# schematic_v_2.net
KiCad netlist of a schematic drawn in EAGLE
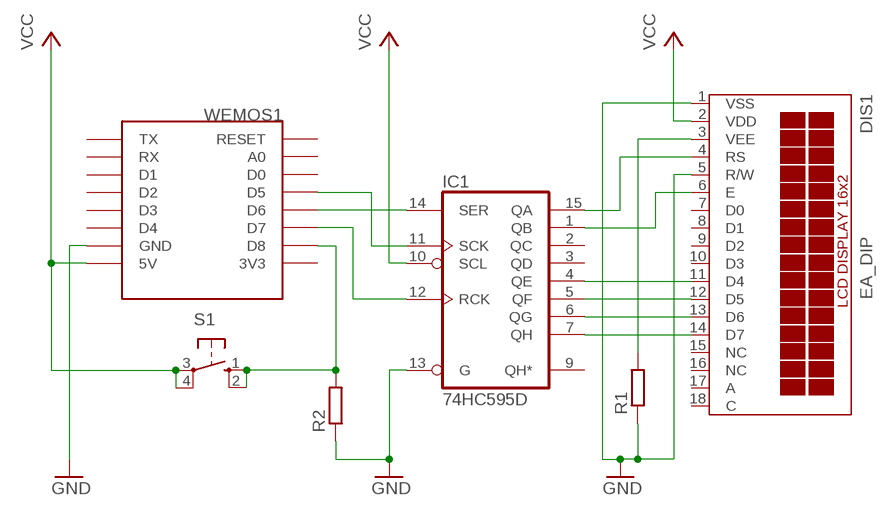
[diagram p0: schematic, sheet 1]

(export (version "E")
  (design (tool "Eeschema 10.0.6"))
  (components
    (comp (ref "DIS1")
      (value "EA_DIP")
      (footprint "eagle-import:EA_DIP")
      (libsource (lib "eagle-import") (part "EA_DIP"))
    )
    (comp (ref "IC1")
      (value "74HC595D")
      (footprint "eagle-import:SO16")
      (libsource (lib "eagle-import") (part "74595DHC"))
    )
    (comp (ref "R1")
      (value "R-EU_0204/2V")
      (footprint "eagle-import:0204V")
      (libsource (lib "eagle-import") (part "R-EU_0204/2V"))
    )
    (comp (ref "R2")
      (value "R-EU_0204/2V")
      (footprint "eagle-import:0204V")
      (libsource (lib "eagle-import") (part "R-EU_0204/2V"))
    )
    (comp (ref "S1")
      (value "10-XX")
      (footprint "eagle-import:B3F-10XX")
      (fields (field (name "MPN") "B3F-1000"))
      (libsource (lib "eagle-import") (part "10-XX"))
    )
    (comp (ref "WEMOS1")
      (value "WEMOS-D1-MINI")
      (footprint "eagle-import:WEMOS-D1-MINI")
      (libsource (lib "eagle-import") (part "WEMOS-D1-MINI"))
    )
  )
  (nets
    (net (code "1") (name "GND") (class "Default")
      (node (ref "DIS1") (pin "1") (pinfunction "VSS_1") (pintype "power_in"))
      (node (ref "DIS1") (pin "5") (pinfunction "R/W_5") (pintype "input"))
      (node (ref "IC1") (pin "13") (pinfunction "G_13") (pintype "input"))
      (node (ref "R1") (pin "1") (pinfunction "1_1") (pintype "passive"))
      (node (ref "R2") (pin "1") (pinfunction "1_1") (pintype "passive"))
      (node (ref "WEMOS1") (pin "GND") (pinfunction "GND_GND") (pintype "bidirectional"))
    )
    (net (code "2") (name "Net-(DIS1-D4)") (class "Default")
      (node (ref "DIS1") (pin "11") (pinfunction "D4_11") (pintype "input"))
      (node (ref "IC1") (pin "4") (pinfunction "QE_4") (pintype "tri_state"))
    )
    (net (code "3") (name "Net-(DIS1-D5)") (class "Default")
      (node (ref "DIS1") (pin "12") (pinfunction "D5_12") (pintype "input"))
      (node (ref "IC1") (pin "5") (pinfunction "QF_5") (pintype "tri_state"))
    )
    (net (code "4") (name "Net-(DIS1-D6)") (class "Default")
      (node (ref "DIS1") (pin "13") (pinfunction "D6_13") (pintype "input"))
      (node (ref "IC1") (pin "6") (pinfunction "QG_6") (pintype "tri_state"))
    )
    (net (code "5") (name "Net-(DIS1-D7)") (class "Default")
      (node (ref "DIS1") (pin "14") (pinfunction "D7_14") (pintype "input"))
      (node (ref "IC1") (pin "7") (pinfunction "QH_7") (pintype "tri_state"))
    )
    (net (code "6") (name "Net-(DIS1-E)") (class "Default")
      (node (ref "DIS1") (pin "6") (pinfunction "E_6") (pintype "input"))
      (node (ref "IC1") (pin "1") (pinfunction "QB_1") (pintype "tri_state"))
    )
    (net (code "7") (name "Net-(DIS1-RS)") (class "Default")
      (node (ref "DIS1") (pin "4") (pinfunction "RS_4") (pintype "input"))
      (node (ref "IC1") (pin "15") (pinfunction "QA_15") (pintype "tri_state"))
    )
    (net (code "8") (name "Net-(DIS1-VEE)") (class "Default")
      (node (ref "DIS1") (pin "3") (pinfunction "VEE_3") (pintype "power_in"))
      (node (ref "R1") (pin "2") (pinfunction "2_2") (pintype "passive"))
    )
    (net (code "9") (name "Net-(IC1A-RCK)") (class "Default")
      (node (ref "IC1") (pin "12") (pinfunction "RCK_12") (pintype "input"))
      (node (ref "WEMOS1") (pin "D7") (pinfunction "D7_D7") (pintype "bidirectional"))
    )
    (net (code "10") (name "Net-(IC1A-SCK)") (class "Default")
      (node (ref "IC1") (pin "11") (pinfunction "SCK_11") (pintype "input"))
      (node (ref "WEMOS1") (pin "D5") (pinfunction "D5_D5") (pintype "bidirectional"))
    )
    (net (code "11") (name "Net-(IC1A-SER)") (class "Default")
      (node (ref "IC1") (pin "14") (pinfunction "SER_14") (pintype "input"))
      (node (ref "WEMOS1") (pin "D6") (pinfunction "D6_D6") (pintype "bidirectional"))
    )
    (net (code "12") (name "Net-(S1-S)") (class "Default")
      (node (ref "R2") (pin "2") (pinfunction "2_2") (pintype "passive"))
      (node (ref "S1") (pin "1") (pinfunction "S_1") (pintype "passive"))
      (node (ref "S1") (pin "2") (pinfunction "S1_2") (pintype "passive"))
      (node (ref "WEMOS1") (pin "D8") (pinfunction "D8_D8") (pintype "bidirectional"))
    )
    (net (code "13") (name "VCC") (class "Default")
      (node (ref "DIS1") (pin "2") (pinfunction "VDD_2") (pintype "power_in"))
      (node (ref "IC1") (pin "10") (pinfunction "SCL_10") (pintype "input"))
      (node (ref "S1") (pin "3") (pinfunction "P_3") (pintype "passive"))
      (node (ref "S1") (pin "4") (pinfunction "P1_4") (pintype "passive"))
      (node (ref "WEMOS1") (pin "5V") (pinfunction "5V_5V") (pintype "bidirectional"))
    )
    (net (code "14") (name "unconnected-(DIS1-A-Pad17)") (class "Default")
      (node (ref "DIS1") (pin "17") (pinfunction "A_17") (pintype "passive"))
    )
    (net (code "15") (name "unconnected-(DIS1-C-Pad18)") (class "Default")
      (node (ref "DIS1") (pin "18") (pinfunction "C_18") (pintype "passive"))
    )
    (net (code "16") (name "unconnected-(DIS1-D0-Pad7)") (class "Default")
      (node (ref "DIS1") (pin "7") (pinfunction "D0_7") (pintype "input"))
    )
    (net (code "17") (name "unconnected-(DIS1-D1-Pad8)") (class "Default")
      (node (ref "DIS1") (pin "8") (pinfunction "D1_8") (pintype "input"))
    )
    (net (code "18") (name "unconnected-(DIS1-D2-Pad9)") (class "Default")
      (node (ref "DIS1") (pin "9") (pinfunction "D2_9") (pintype "input"))
    )
    (net (code "19") (name "unconnected-(DIS1-D3-Pad10)") (class "Default")
      (node (ref "DIS1") (pin "10") (pinfunction "D3_10") (pintype "input"))
    )
    (net (code "20") (name "unconnected-(DIS1-NC-Pad15)") (class "Default")
      (node (ref "DIS1") (pin "15") (pinfunction "NC_15") (pintype "no_connect"))
    )
    (net (code "21") (name "unconnected-(DIS1-NC-Pad16)") (class "Default")
      (node (ref "DIS1") (pin "16") (pinfunction "NC_16") (pintype "no_connect"))
    )
    (net (code "22") (name "unconnected-(IC1A-QC-Pad2)") (class "Default")
      (node (ref "IC1") (pin "2") (pinfunction "QC_2") (pintype "tri_state"))
    )
    (net (code "23") (name "unconnected-(IC1A-QD-Pad3)") (class "Default")
      (node (ref "IC1") (pin "3") (pinfunction "QD_3") (pintype "tri_state"))
    )
    (net (code "24") (name "unconnected-(IC1A-QH*-Pad9)") (class "Default")
      (node (ref "IC1") (pin "9") (pinfunction "QH*_9") (pintype "tri_state"))
    )
    (net (code "25") (name "unconnected-(WEMOS1-Pad3V3)") (class "Default")
      (node (ref "WEMOS1") (pin "3V3") (pinfunction "3V3_3V3") (pintype "bidirectional"))
    )
    (net (code "26") (name "unconnected-(WEMOS1-PadA0)") (class "Default")
      (node (ref "WEMOS1") (pin "A0") (pinfunction "A0_A0") (pintype "bidirectional"))
    )
    (net (code "27") (name "unconnected-(WEMOS1-PadD0)") (class "Default")
      (node (ref "WEMOS1") (pin "D0") (pinfunction "D0_D0") (pintype "bidirectional"))
    )
    (net (code "28") (name "unconnected-(WEMOS1-PadD1)") (class "Default")
      (node (ref "WEMOS1") (pin "D1") (pinfunction "D1_D1") (pintype "bidirectional"))
    )
    (net (code "29") (name "unconnected-(WEMOS1-PadD2)") (class "Default")
      (node (ref "WEMOS1") (pin "D2") (pinfunction "D2_D2") (pintype "bidirectional"))
    )
    (net (code "30") (name "unconnected-(WEMOS1-PadD3)") (class "Default")
      (node (ref "WEMOS1") (pin "D3") (pinfunction "D3_D3") (pintype "bidirectional"))
    )
    (net (code "31") (name "unconnected-(WEMOS1-PadD4)") (class "Default")
      (node (ref "WEMOS1") (pin "D4") (pinfunction "D4_D4") (pintype "bidirectional"))
    )
    (net (code "32") (name "unconnected-(WEMOS1-PadRESET)") (class "Default")
      (node (ref "WEMOS1") (pin "RESET") (pinfunction "RESET_RESET") (pintype "bidirectional"))
    )
    (net (code "33") (name "unconnected-(WEMOS1-PadRX)") (class "Default")
      (node (ref "WEMOS1") (pin "RX") (pinfunction "RX_RX") (pintype "bidirectional"))
    )
    (net (code "34") (name "unconnected-(WEMOS1-PadTX)") (class "Default")
      (node (ref "WEMOS1") (pin "TX") (pinfunction "TX_TX") (pintype "bidirectional"))
    )
  )
)
